# FAROS_DE_LUZ.net
KiCad netlist of a schematic drawn in EAGLE
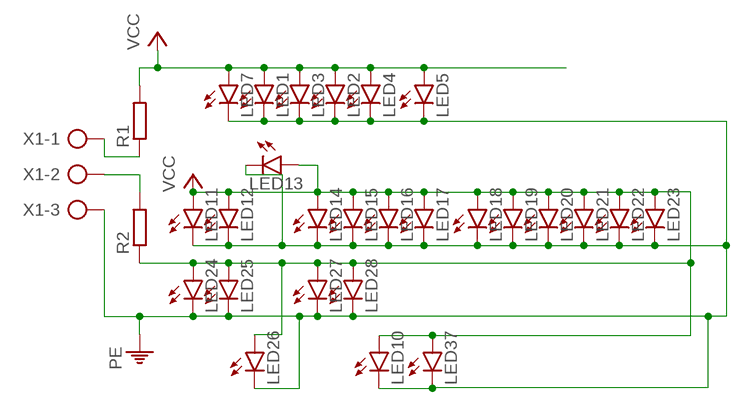
[diagram p0: schematic, sheet 1]

(export (version "E")
  (design (tool "Eeschema 10.0.6"))
  (components
    (comp (ref "LED1")
      (value "LED10MM")
      (footprint "eagle-import:LED10MM")
      (libsource (lib "eagle-import") (part "LED10MM"))
    )
    (comp (ref "LED2")
      (value "LED10MM")
      (footprint "eagle-import:LED10MM")
      (libsource (lib "eagle-import") (part "LED10MM"))
    )
    (comp (ref "LED3")
      (value "LED10MM")
      (footprint "eagle-import:LED10MM")
      (libsource (lib "eagle-import") (part "LED10MM"))
    )
    (comp (ref "LED4")
      (value "LED10MM")
      (footprint "eagle-import:LED10MM")
      (libsource (lib "eagle-import") (part "LED10MM"))
    )
    (comp (ref "LED5")
      (value "LED10MM")
      (footprint "eagle-import:LED10MM")
      (libsource (lib "eagle-import") (part "LED10MM"))
    )
    (comp (ref "LED7")
      (value "LED10MM")
      (footprint "eagle-import:LED10MM")
      (libsource (lib "eagle-import") (part "LED10MM"))
    )
    (comp (ref "LED10")
      (value "LED5MM")
      (footprint "eagle-import:LED5MM")
      (libsource (lib "eagle-import") (part "LED5MM"))
    )
    (comp (ref "LED11")
      (value "LED5MM")
      (footprint "eagle-import:LED5MM")
      (libsource (lib "eagle-import") (part "LED5MM"))
    )
    (comp (ref "LED12")
      (value "LED5MM")
      (footprint "eagle-import:LED5MM")
      (libsource (lib "eagle-import") (part "LED5MM"))
    )
    (comp (ref "LED13")
      (value "LED5MM")
      (footprint "eagle-import:LED5MM")
      (libsource (lib "eagle-import") (part "LED5MM"))
    )
    (comp (ref "LED14")
      (value "LED5MM")
      (footprint "eagle-import:LED5MM")
      (libsource (lib "eagle-import") (part "LED5MM"))
    )
    (comp (ref "LED15")
      (value "LED5MM")
      (footprint "eagle-import:LED5MM")
      (libsource (lib "eagle-import") (part "LED5MM"))
    )
    (comp (ref "LED16")
      (value "LED5MM")
      (footprint "eagle-import:LED5MM")
      (libsource (lib "eagle-import") (part "LED5MM"))
    )
    (comp (ref "LED17")
      (value "LED5MM")
      (footprint "eagle-import:LED5MM")
      (libsource (lib "eagle-import") (part "LED5MM"))
    )
    (comp (ref "LED18")
      (value "LED5MM")
      (footprint "eagle-import:LED5MM")
      (libsource (lib "eagle-import") (part "LED5MM"))
    )
    (comp (ref "LED19")
      (value "LED5MM")
      (footprint "eagle-import:LED5MM")
      (libsource (lib "eagle-import") (part "LED5MM"))
    )
    (comp (ref "LED20")
      (value "LED5MM")
      (footprint "eagle-import:LED5MM")
      (libsource (lib "eagle-import") (part "LED5MM"))
    )
    (comp (ref "LED21")
      (value "LED5MM")
      (footprint "eagle-import:LED5MM")
      (libsource (lib "eagle-import") (part "LED5MM"))
    )
    (comp (ref "LED22")
      (value "LED5MM")
      (footprint "eagle-import:LED5MM")
      (libsource (lib "eagle-import") (part "LED5MM"))
    )
    (comp (ref "LED23")
      (value "LED5MM")
      (footprint "eagle-import:LED5MM")
      (libsource (lib "eagle-import") (part "LED5MM"))
    )
    (comp (ref "LED24")
      (value "LED5MM")
      (footprint "eagle-import:LED5MM")
      (libsource (lib "eagle-import") (part "LED5MM"))
    )
    (comp (ref "LED25")
      (value "LED5MM")
      (footprint "eagle-import:LED5MM")
      (libsource (lib "eagle-import") (part "LED5MM"))
    )
    (comp (ref "LED26")
      (value "LED5MM")
      (footprint "eagle-import:LED5MM")
      (libsource (lib "eagle-import") (part "LED5MM"))
    )
    (comp (ref "LED27")
      (value "LED5MM")
      (footprint "eagle-import:LED5MM")
      (libsource (lib "eagle-import") (part "LED5MM"))
    )
    (comp (ref "LED28")
      (value "LED5MM")
      (footprint "eagle-import:LED5MM")
      (libsource (lib "eagle-import") (part "LED5MM"))
    )
    (comp (ref "LED37")
      (value "LED5MM")
      (footprint "eagle-import:LED5MM")
      (libsource (lib "eagle-import") (part "LED5MM"))
    )
    (comp (ref "R1")
      (value "R-EU_0204/7")
      (footprint "eagle-import:0204_7")
      (libsource (lib "eagle-import") (part "R-EU_0204/7"))
    )
    (comp (ref "R2")
      (value "R-EU_0204/7")
      (footprint "eagle-import:0204_7")
      (libsource (lib "eagle-import") (part "R-EU_0204/7"))
    )
    (comp (ref "X1")
      (value "AK500/3-H")
      (footprint "eagle-import:AK500_3-H")
      (libsource (lib "eagle-import") (part "AK500/3-H"))
    )
  )
  (nets
    (net (code "1") (name "Net-(X1A-KL)") (class "Default")
      (node (ref "R1") (pin "1") (pinfunction "1_1") (pintype "passive"))
      (node (ref "X1") (pin "1") (pinfunction "KL_1") (pintype "passive"))
    )
    (net (code "2") (name "Net-(X1B-KL)") (class "Default")
      (node (ref "R2") (pin "2") (pinfunction "2_2") (pintype "passive"))
      (node (ref "X1") (pin "2") (pinfunction "KL_2") (pintype "passive"))
    )
    (net (code "3") (name "PE") (class "Default")
      (node (ref "LED1") (pin "K") (pinfunction "C_K") (pintype "passive"))
      (node (ref "LED10") (pin "K") (pinfunction "C_K") (pintype "passive"))
      (node (ref "LED11") (pin "K") (pinfunction "C_K") (pintype "passive"))
      (node (ref "LED12") (pin "K") (pinfunction "C_K") (pintype "passive"))
      (node (ref "LED13") (pin "K") (pinfunction "C_K") (pintype "passive"))
      (node (ref "LED14") (pin "K") (pinfunction "C_K") (pintype "passive"))
      (node (ref "LED15") (pin "K") (pinfunction "C_K") (pintype "passive"))
      (node (ref "LED16") (pin "K") (pinfunction "C_K") (pintype "passive"))
      (node (ref "LED17") (pin "K") (pinfunction "C_K") (pintype "passive"))
      (node (ref "LED18") (pin "K") (pinfunction "C_K") (pintype "passive"))
      (node (ref "LED19") (pin "K") (pinfunction "C_K") (pintype "passive"))
      (node (ref "LED2") (pin "K") (pinfunction "C_K") (pintype "passive"))
      (node (ref "LED20") (pin "K") (pinfunction "C_K") (pintype "passive"))
      (node (ref "LED21") (pin "K") (pinfunction "C_K") (pintype "passive"))
      (node (ref "LED22") (pin "K") (pinfunction "C_K") (pintype "passive"))
      (node (ref "LED23") (pin "K") (pinfunction "C_K") (pintype "passive"))
      (node (ref "LED24") (pin "K") (pinfunction "C_K") (pintype "passive"))
      (node (ref "LED25") (pin "K") (pinfunction "C_K") (pintype "passive"))
      (node (ref "LED26") (pin "K") (pinfunction "C_K") (pintype "passive"))
      (node (ref "LED27") (pin "K") (pinfunction "C_K") (pintype "passive"))
      (node (ref "LED28") (pin "K") (pinfunction "C_K") (pintype "passive"))
      (node (ref "LED3") (pin "K") (pinfunction "C_K") (pintype "passive"))
      (node (ref "LED37") (pin "K") (pinfunction "C_K") (pintype "passive"))
      (node (ref "LED4") (pin "K") (pinfunction "C_K") (pintype "passive"))
      (node (ref "LED5") (pin "K") (pinfunction "C_K") (pintype "passive"))
      (node (ref "LED7") (pin "K") (pinfunction "C_K") (pintype "passive"))
      (node (ref "X1") (pin "3") (pinfunction "KL_3") (pintype "passive"))
    )
    (net (code "4") (name "VCC") (class "Default")
      (node (ref "LED1") (pin "A") (pinfunction "A_A") (pintype "passive"))
      (node (ref "LED10") (pin "A") (pinfunction "A_A") (pintype "passive"))
      (node (ref "LED11") (pin "A") (pinfunction "A_A") (pintype "passive"))
      (node (ref "LED12") (pin "A") (pinfunction "A_A") (pintype "passive"))
      (node (ref "LED13") (pin "A") (pinfunction "A_A") (pintype "passive"))
      (node (ref "LED14") (pin "A") (pinfunction "A_A") (pintype "passive"))
      (node (ref "LED15") (pin "A") (pinfunction "A_A") (pintype "passive"))
      (node (ref "LED16") (pin "A") (pinfunction "A_A") (pintype "passive"))
      (node (ref "LED17") (pin "A") (pinfunction "A_A") (pintype "passive"))
      (node (ref "LED18") (pin "A") (pinfunction "A_A") (pintype "passive"))
      (node (ref "LED19") (pin "A") (pinfunction "A_A") (pintype "passive"))
      (node (ref "LED2") (pin "A") (pinfunction "A_A") (pintype "passive"))
      (node (ref "LED20") (pin "A") (pinfunction "A_A") (pintype "passive"))
      (node (ref "LED21") (pin "A") (pinfunction "A_A") (pintype "passive"))
      (node (ref "LED22") (pin "A") (pinfunction "A_A") (pintype "passive"))
      (node (ref "LED23") (pin "A") (pinfunction "A_A") (pintype "passive"))
      (node (ref "LED24") (pin "A") (pinfunction "A_A") (pintype "passive"))
      (node (ref "LED25") (pin "A") (pinfunction "A_A") (pintype "passive"))
      (node (ref "LED26") (pin "A") (pinfunction "A_A") (pintype "passive"))
      (node (ref "LED27") (pin "A") (pinfunction "A_A") (pintype "passive"))
      (node (ref "LED28") (pin "A") (pinfunction "A_A") (pintype "passive"))
      (node (ref "LED3") (pin "A") (pinfunction "A_A") (pintype "passive"))
      (node (ref "LED37") (pin "A") (pinfunction "A_A") (pintype "passive"))
      (node (ref "LED4") (pin "A") (pinfunction "A_A") (pintype "passive"))
      (node (ref "LED5") (pin "A") (pinfunction "A_A") (pintype "passive"))
      (node (ref "LED7") (pin "A") (pinfunction "A_A") (pintype "passive"))
      (node (ref "R1") (pin "2") (pinfunction "2_2") (pintype "passive"))
      (node (ref "R2") (pin "1") (pinfunction "1_1") (pintype "passive"))
    )
  )
)
